# GPV1.net
KiCad netlist of a schematic drawn in EAGLE
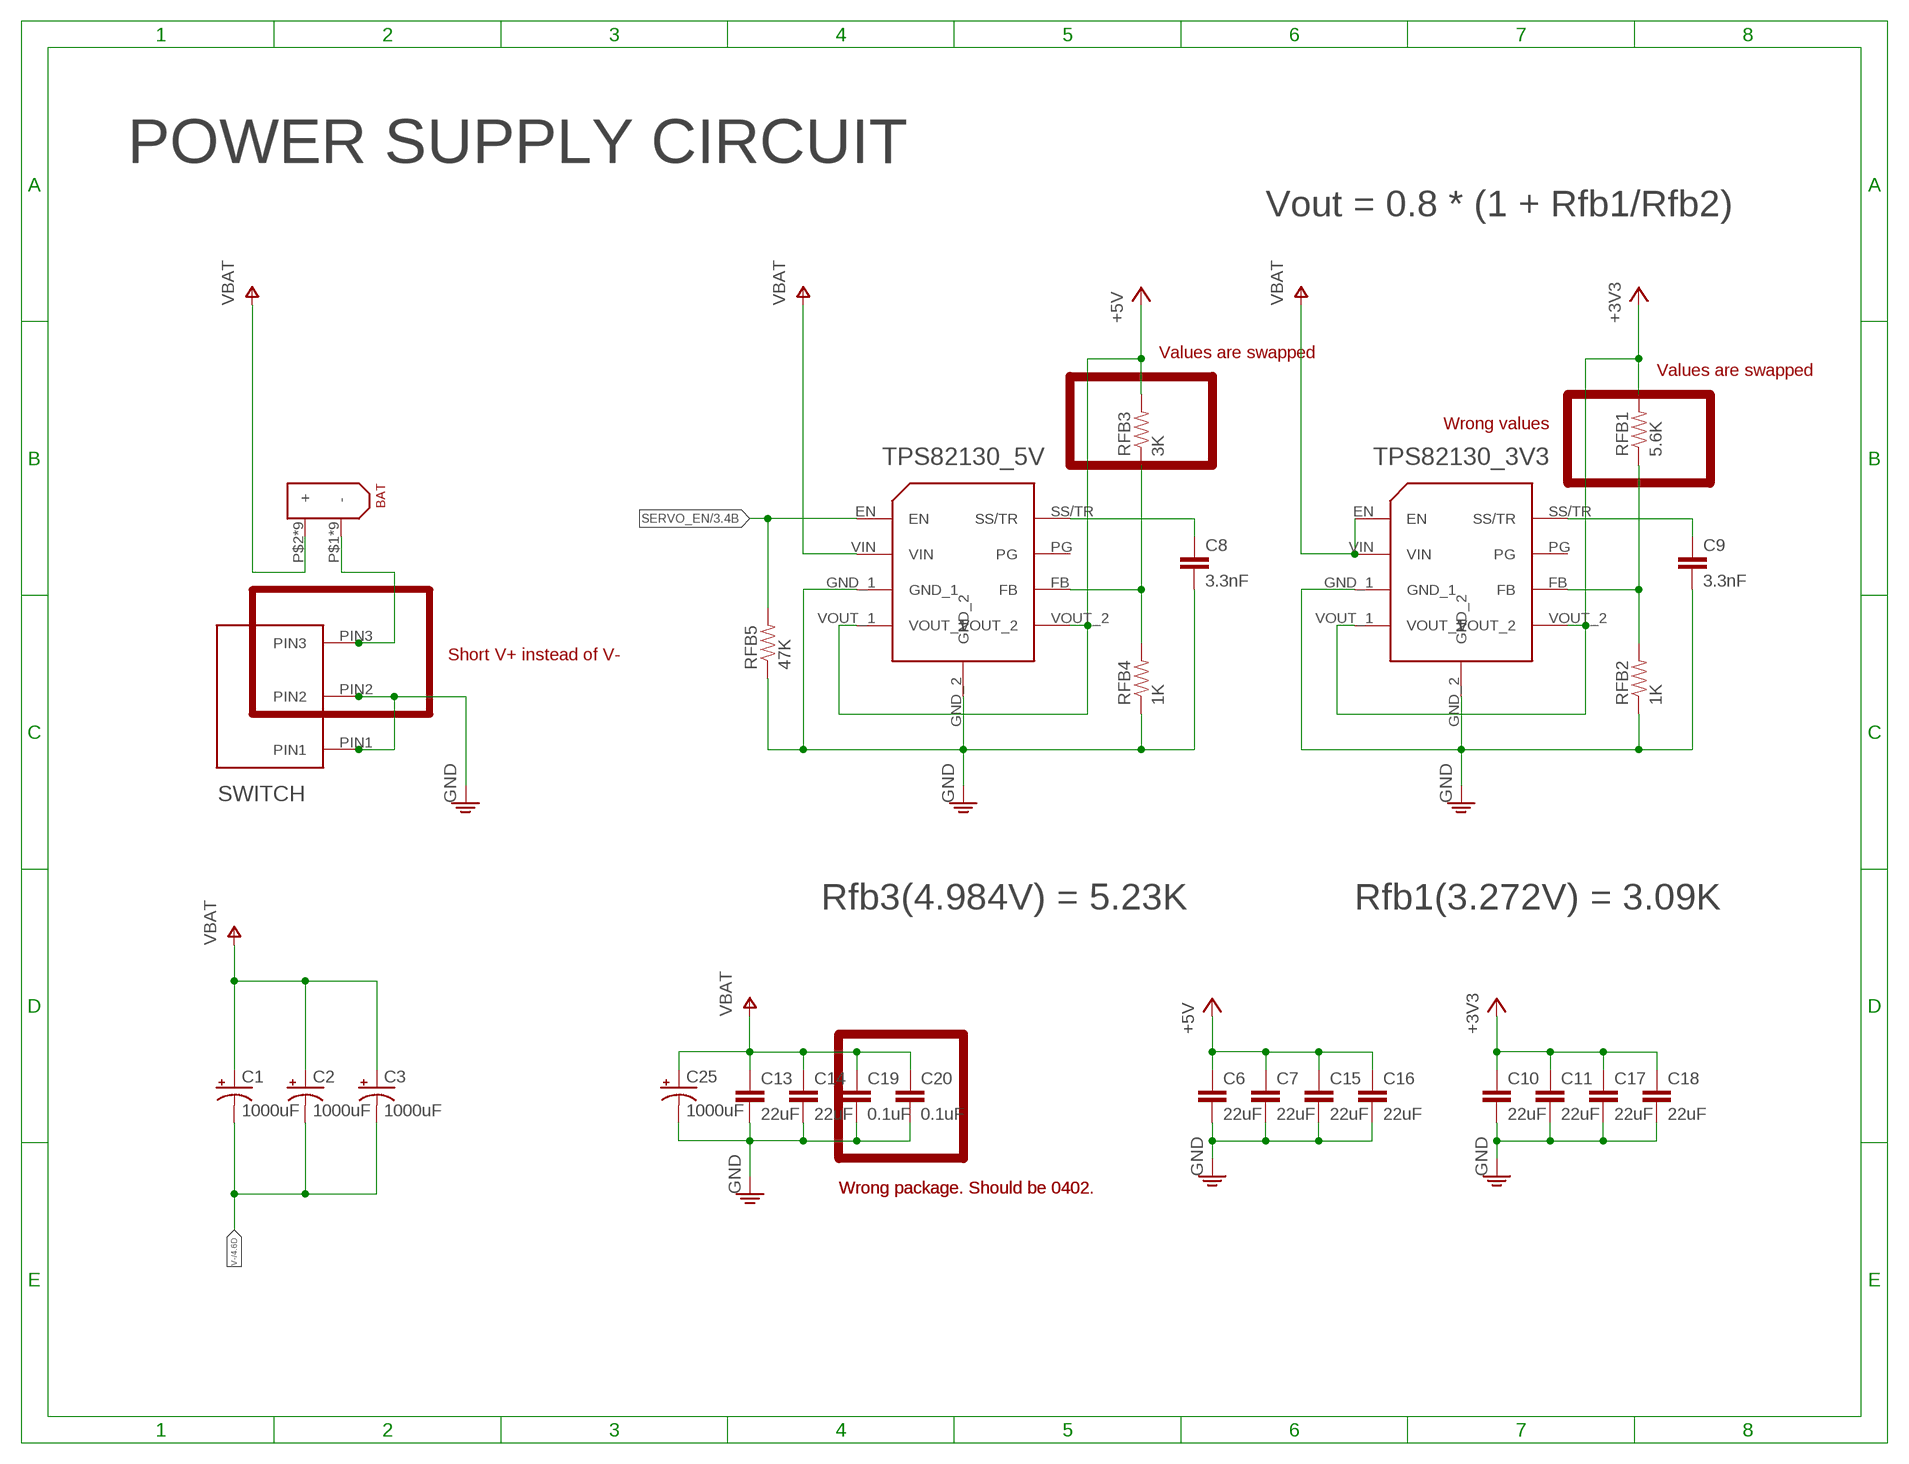
[diagram p0: schematic, sheet 1]
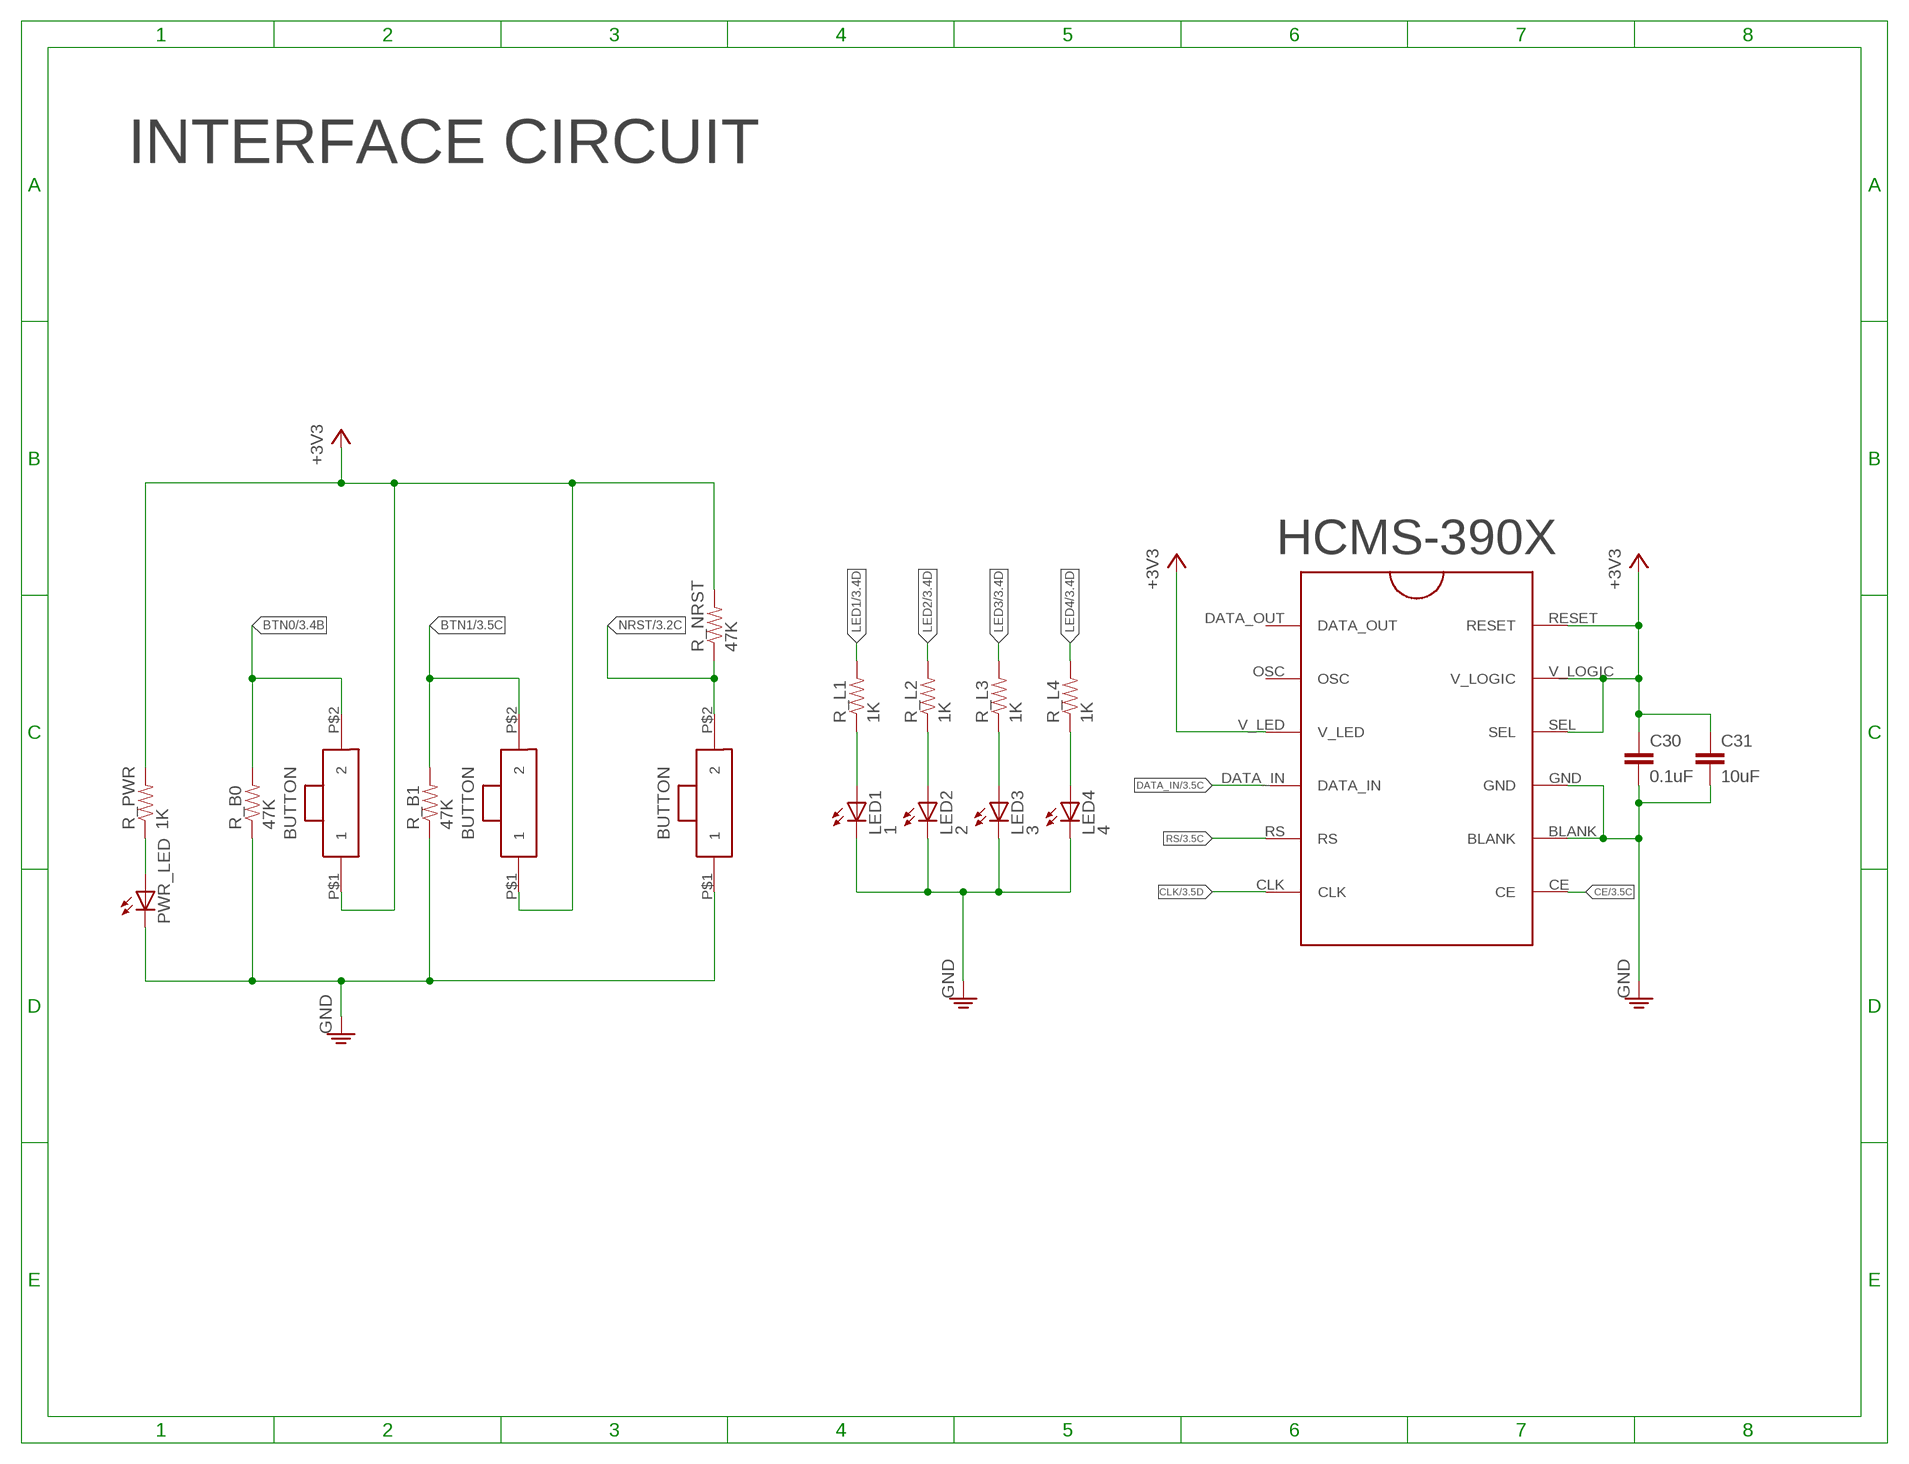
[diagram p1: schematic, sheet 2]
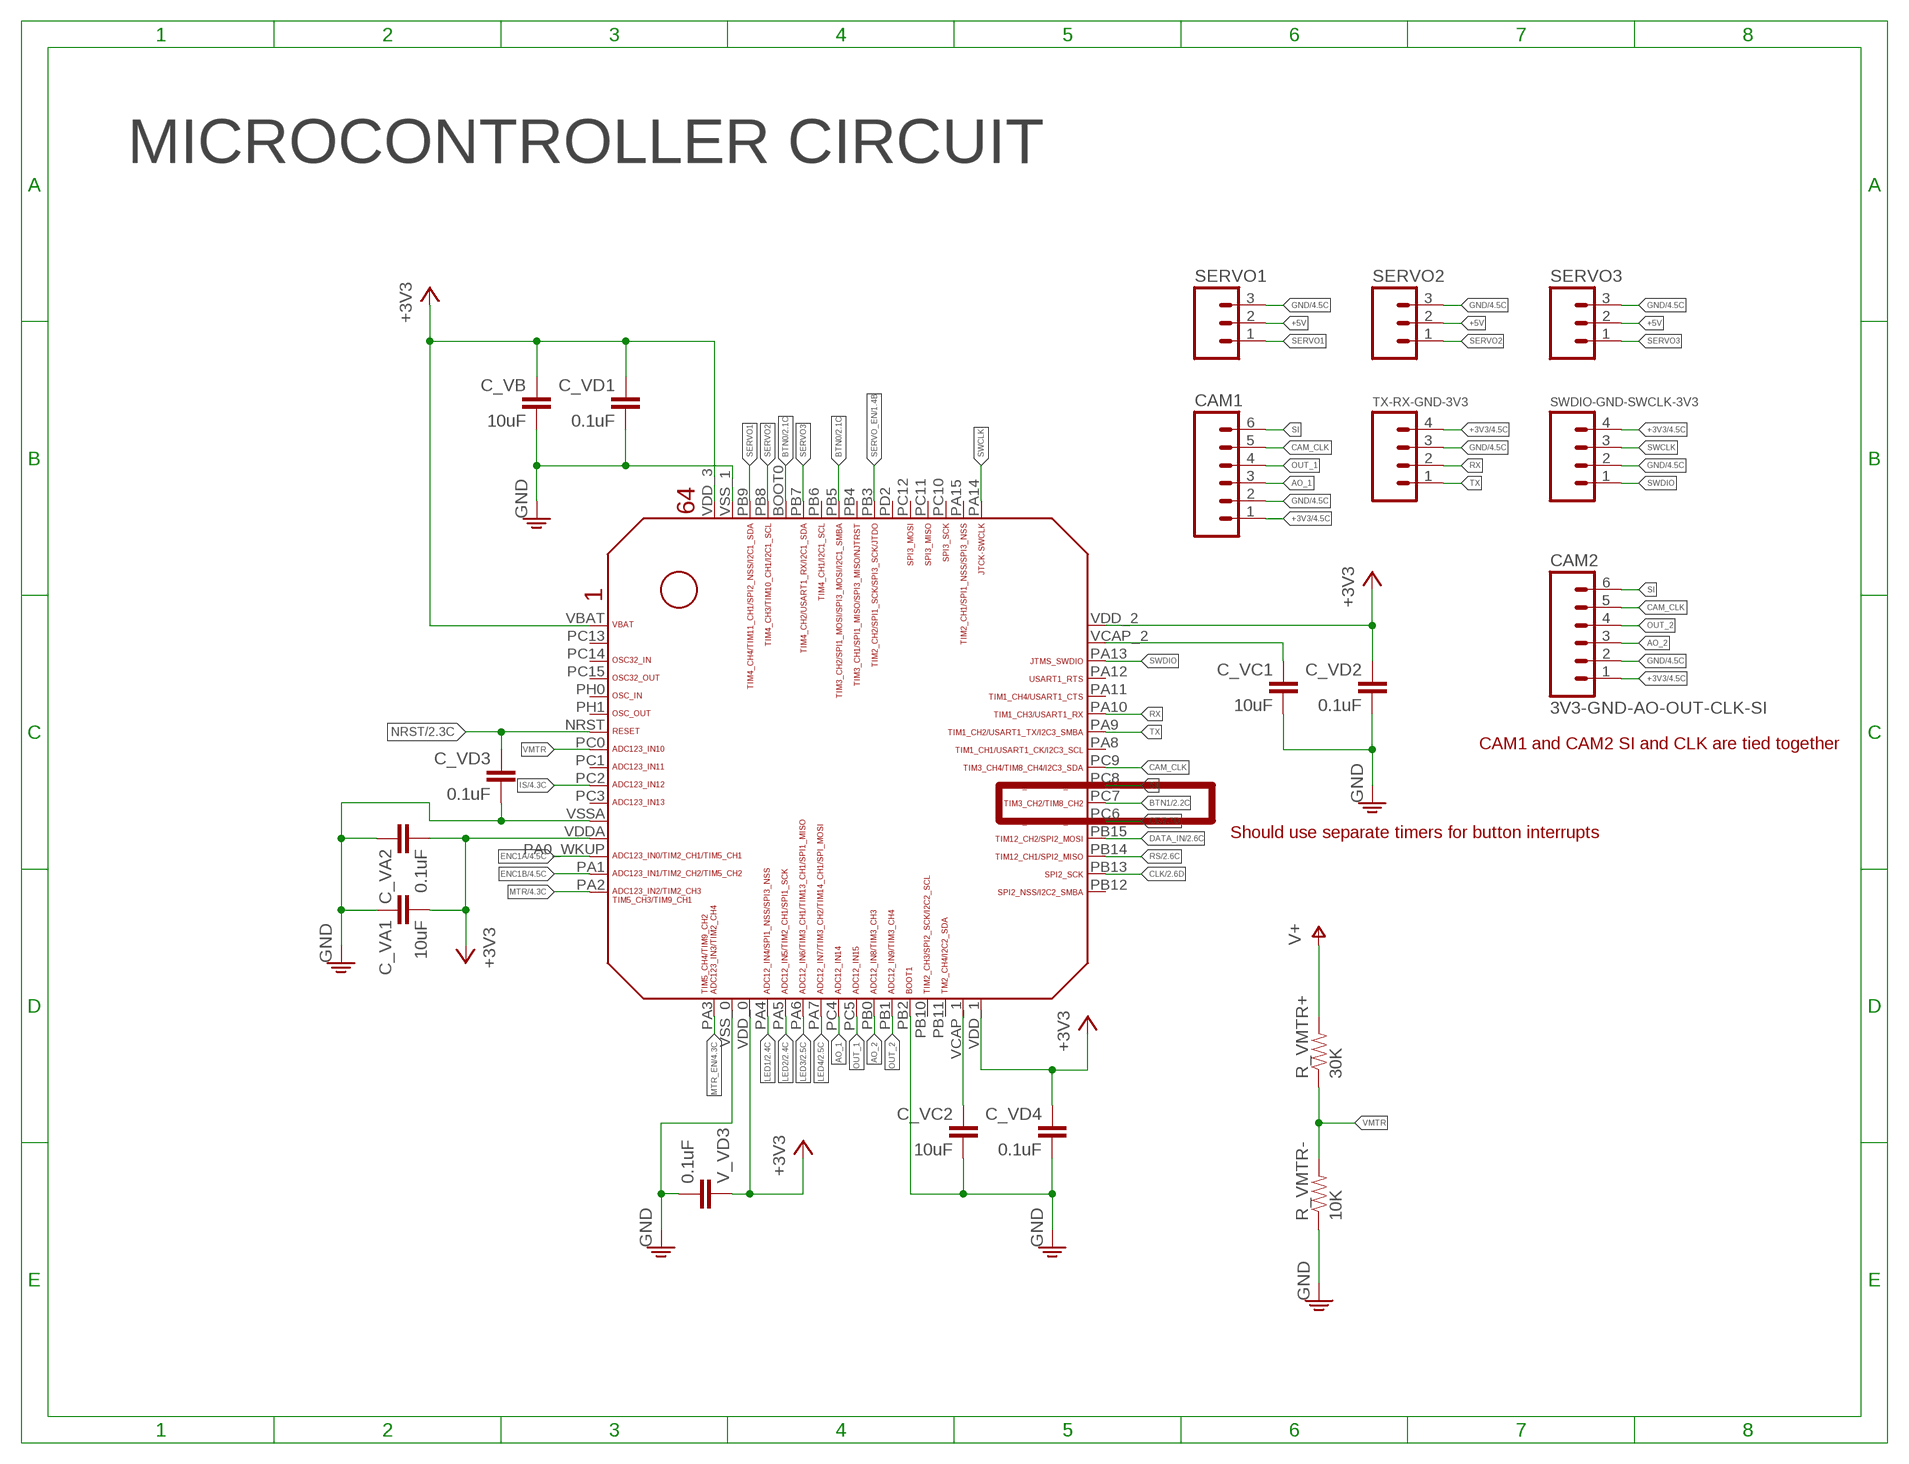
[diagram p2: schematic, sheet 3]
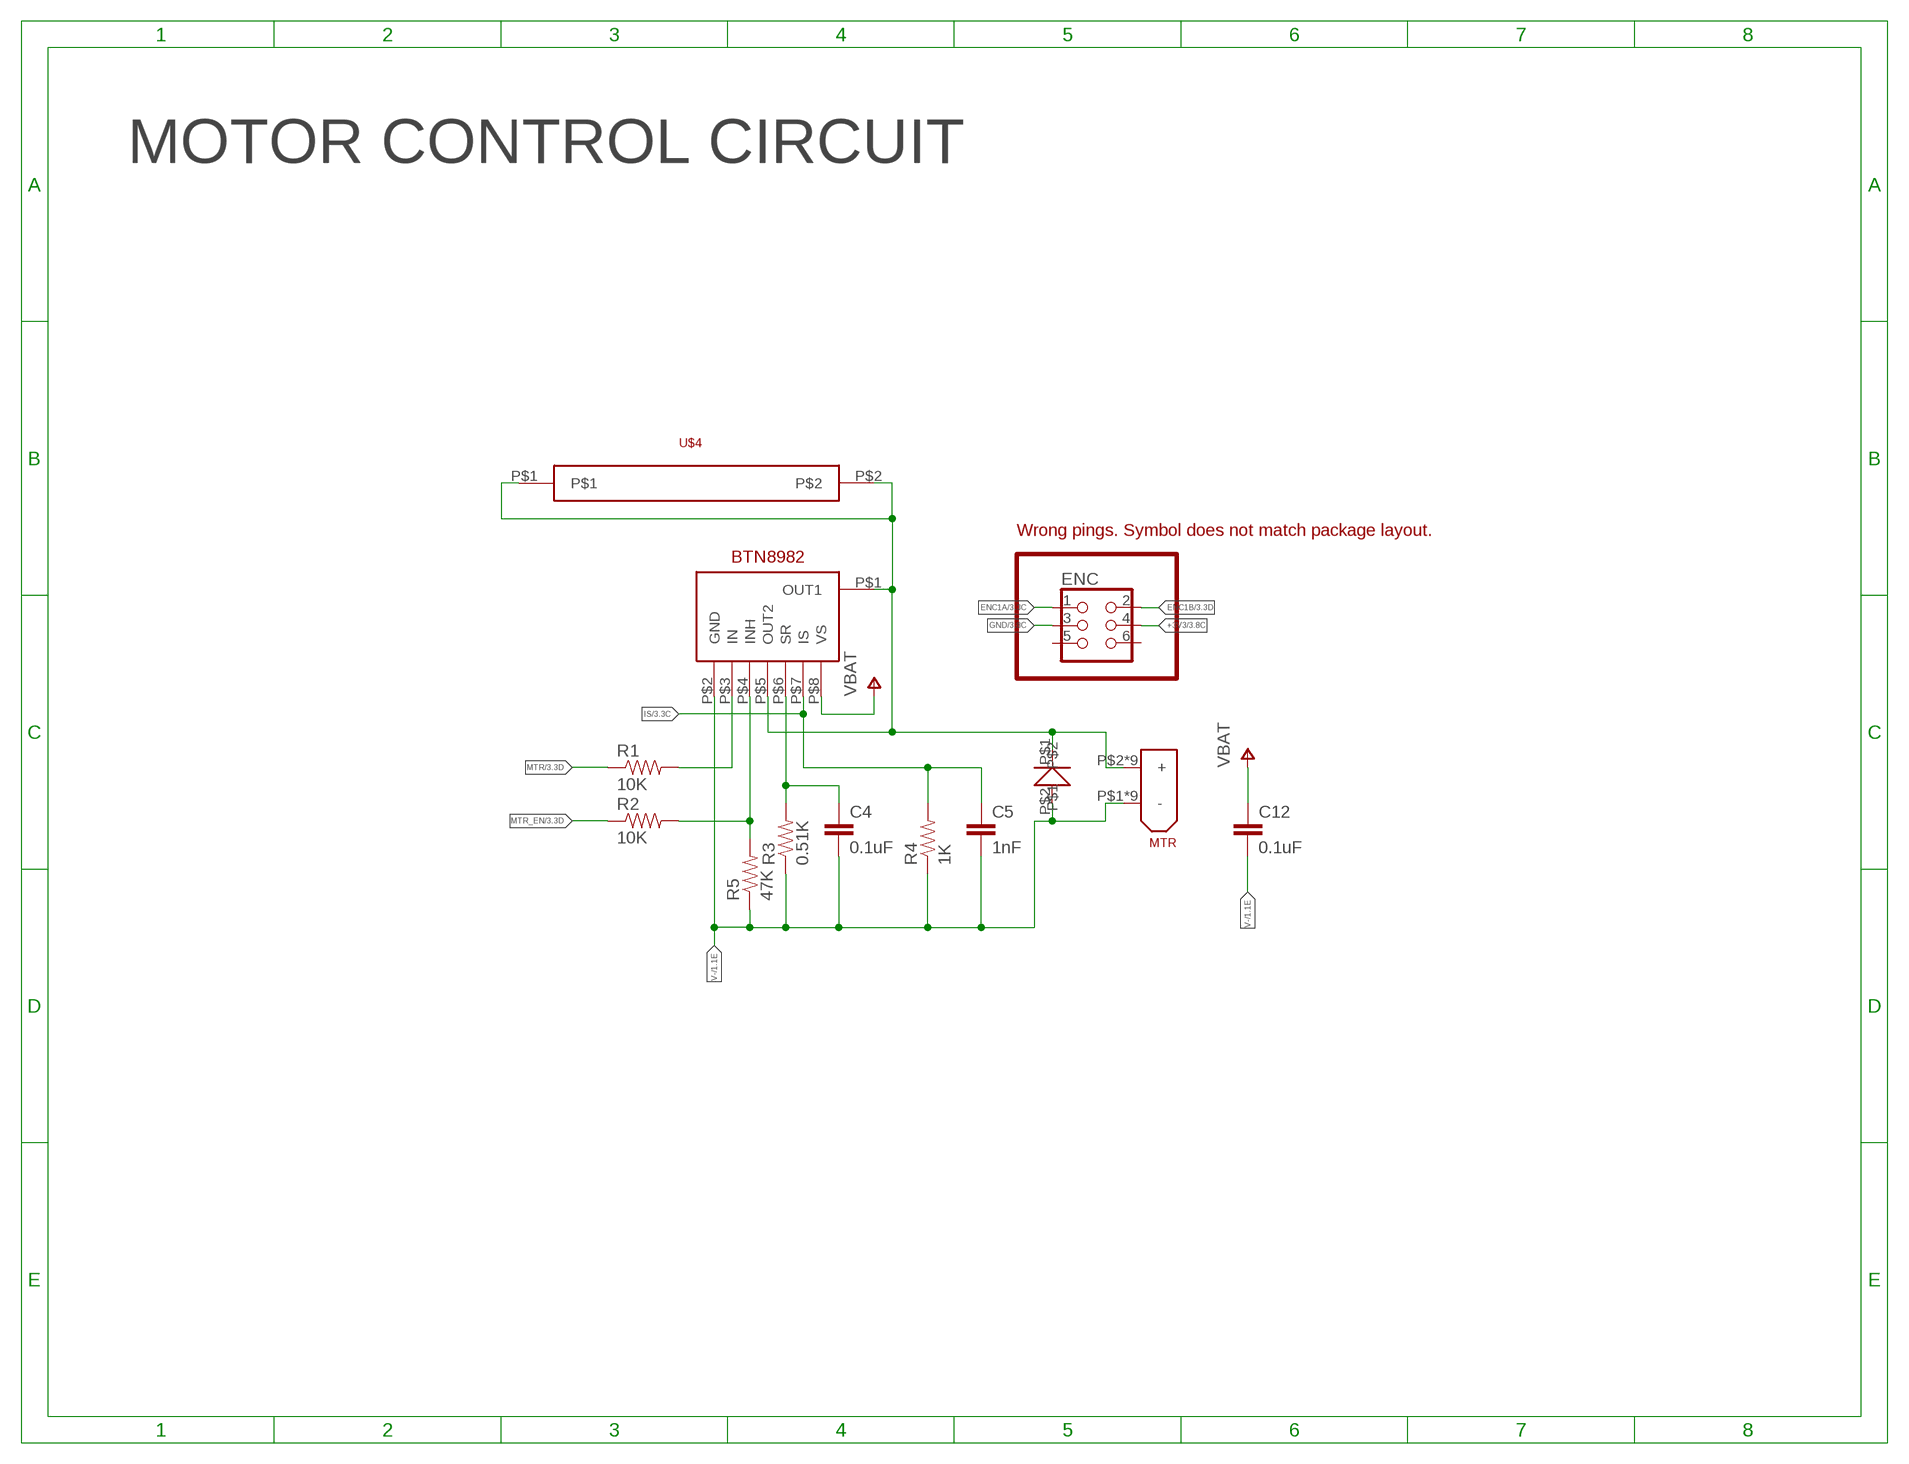
[diagram p3: schematic, sheet 4]

(export (version "E")
  (design (tool "Eeschema 10.0.6"))
  (components
    (comp (ref "BTN0")
      (value "POLOLU_BUTTON")
      (footprint "eagle-import:POLOLU_BUTTON")
      (libsource (lib "eagle-import") (part "POLOLU_BUTTON"))
    )
    (comp (ref "BTN1")
      (value "POLOLU_BUTTON")
      (footprint "eagle-import:POLOLU_BUTTON")
      (libsource (lib "eagle-import") (part "POLOLU_BUTTON"))
    )
    (comp (ref "C30")
      (value "0.1uF")
      (footprint "eagle-import:0402-CAP")
      (libsource (lib "eagle-import") (part "CAP0402-CAP"))
    )
    (comp (ref "C31")
      (value "10uF")
      (footprint "eagle-import:0402-CAP")
      (libsource (lib "eagle-import") (part "CAP0402-CAP"))
    )
    (comp (ref "HCMS-390X")
      (value "HCMS-390X")
      (footprint "eagle-import:HCMS-2903")
      (libsource (lib "eagle-import") (part "HCMS-2903"))
    )
    (comp (ref "LED1")
      (value "1")
      (footprint "eagle-import:LED-0603")
      (libsource (lib "eagle-import") (part "LED0603"))
    )
    (comp (ref "LED2")
      (value "2")
      (footprint "eagle-import:LED-0603")
      (libsource (lib "eagle-import") (part "LED0603"))
    )
    (comp (ref "LED3")
      (value "3")
      (footprint "eagle-import:LED-0603")
      (libsource (lib "eagle-import") (part "LED0603"))
    )
    (comp (ref "LED4")
      (value "4")
      (footprint "eagle-import:LED-0603")
      (libsource (lib "eagle-import") (part "LED0603"))
    )
    (comp (ref "PWR_LED")
      (value "LED0603")
      (footprint "eagle-import:LED-0603")
      (libsource (lib "eagle-import") (part "LED0603"))
    )
    (comp (ref "RESET")
      (value "NRST")
      (footprint "eagle-import:POLOLU_BUTTON")
      (libsource (lib "eagle-import") (part "POLOLU_BUTTON"))
    )
    (comp (ref "R_B0")
      (value "47K")
      (footprint "eagle-import:0402-RES")
      (libsource (lib "eagle-import") (part "RESISTOR0402-RES"))
    )
    (comp (ref "R_B1")
      (value "47K")
      (footprint "eagle-import:0402-RES")
      (libsource (lib "eagle-import") (part "RESISTOR0402-RES"))
    )
    (comp (ref "R_L1")
      (value "1K")
      (footprint "eagle-import:0402-RES")
      (libsource (lib "eagle-import") (part "RESISTOR0402-RES"))
    )
    (comp (ref "R_L2")
      (value "1K")
      (footprint "eagle-import:0402-RES")
      (libsource (lib "eagle-import") (part "RESISTOR0402-RES"))
    )
    (comp (ref "R_L3")
      (value "1K")
      (footprint "eagle-import:0402-RES")
      (libsource (lib "eagle-import") (part "RESISTOR0402-RES"))
    )
    (comp (ref "R_L4")
      (value "1K")
      (footprint "eagle-import:0402-RES")
      (libsource (lib "eagle-import") (part "RESISTOR0402-RES"))
    )
    (comp (ref "R_NRST")
      (value "47K")
      (footprint "eagle-import:0402-RES")
      (libsource (lib "eagle-import") (part "RESISTOR0402-RES"))
    )
    (comp (ref "R_PWR")
      (value "1K")
      (footprint "eagle-import:0402-RES")
      (libsource (lib "eagle-import") (part "RESISTOR0402-RES"))
    )
    (comp (ref "CAM1")
      (value "M06SIP")
      (footprint "eagle-import:1X06")
      (libsource (lib "eagle-import") (part "M06SIP"))
    )
    (comp (ref "CAM2")
      (value "3V3-GND-AO-OUT-CLK-SI")
      (footprint "eagle-import:1X06")
      (libsource (lib "eagle-import") (part "M06SIP"))
    )
    (comp (ref "C_VA1")
      (value "10uF")
      (footprint "eagle-import:0402-CAP")
      (libsource (lib "eagle-import") (part "CAP0402-CAP"))
    )
    (comp (ref "C_VA2")
      (value "0.1uF")
      (footprint "eagle-import:0402-CAP")
      (libsource (lib "eagle-import") (part "CAP0402-CAP"))
    )
    (comp (ref "C_VB")
      (value "10uF")
      (footprint "eagle-import:0402-CAP")
      (libsource (lib "eagle-import") (part "CAP0402-CAP"))
    )
    (comp (ref "C_VC1")
      (value "10uF")
      (footprint "eagle-import:0402-CAP")
      (libsource (lib "eagle-import") (part "CAP0402-CAP"))
    )
    (comp (ref "C_VC2")
      (value "10uF")
      (footprint "eagle-import:0402-CAP")
      (libsource (lib "eagle-import") (part "CAP0402-CAP"))
    )
    (comp (ref "C_VD1")
      (value "0.1uF")
      (footprint "eagle-import:0402-CAP")
      (libsource (lib "eagle-import") (part "CAP0402-CAP"))
    )
    (comp (ref "C_VD2")
      (value "0.1uF")
      (footprint "eagle-import:0402-CAP")
      (libsource (lib "eagle-import") (part "CAP0402-CAP"))
    )
    (comp (ref "C_VD3")
      (value "0.1uF")
      (footprint "eagle-import:0402-CAP")
      (libsource (lib "eagle-import") (part "CAP0402-CAP"))
    )
    (comp (ref "C_VD4")
      (value "0.1uF")
      (footprint "eagle-import:0402-CAP")
      (libsource (lib "eagle-import") (part "CAP0402-CAP"))
    )
    (comp (ref "R_VMTR+")
      (value "30K")
      (footprint "eagle-import:0402-RES")
      (libsource (lib "eagle-import") (part "RESISTOR0402-RES"))
    )
    (comp (ref "R_VMTR-")
      (value "10K")
      (footprint "eagle-import:0402-RES")
      (libsource (lib "eagle-import") (part "RESISTOR0402-RES"))
    )
    (comp (ref "SERVO1")
      (value "M03PTH")
      (footprint "eagle-import:1X03")
      (libsource (lib "eagle-import") (part "M03PTH"))
    )
    (comp (ref "SERVO2")
      (value "M03PTH")
      (footprint "eagle-import:1X03")
      (libsource (lib "eagle-import") (part "M03PTH"))
    )
    (comp (ref "SERVO3")
      (value "M03PTH")
      (footprint "eagle-import:1X03")
      (libsource (lib "eagle-import") (part "M03PTH"))
    )
    (comp (ref "STM32F4X5RG")
      (value "STM32F405/415_LQFP64")
      (footprint "eagle-import:STM32F405_415_LQFP64")
      (libsource (lib "eagle-import") (part "STM32F405/415_LQFP64"))
    )
    (comp (ref "SWDIO-GND-SWCLK-3V3")
      (value "M04PTH")
      (footprint "eagle-import:1X04")
      (libsource (lib "eagle-import") (part "M04PTH"))
    )
    (comp (ref "TX-RX-GND-3V3")
      (value "M04PTH")
      (footprint "eagle-import:1X04")
      (libsource (lib "eagle-import") (part "M04PTH"))
    )
    (comp (ref "V_VD3")
      (value "0.1uF")
      (footprint "eagle-import:0402-CAP")
      (libsource (lib "eagle-import") (part "CAP0402-CAP"))
    )
    (comp (ref "BTN8982")
      (value "BTN8982")
      (footprint "eagle-import:BTN8982")
      (libsource (lib "eagle-import") (part "BTN8982"))
    )
    (comp (ref "C4")
      (value "0.1uF")
      (footprint "eagle-import:0402-CAP")
      (libsource (lib "eagle-import") (part "CAP0402-CAP"))
    )
    (comp (ref "C5")
      (value "1nF")
      (footprint "eagle-import:0402-CAP")
      (libsource (lib "eagle-import") (part "CAP0402-CAP"))
    )
    (comp (ref "C12")
      (value "0.1uF")
      (footprint "eagle-import:0402-CAP")
      (libsource (lib "eagle-import") (part "CAP0402-CAP"))
    )
    (comp (ref "DIODE")
      (value "DIODE_DO-214AB")
      (footprint "eagle-import:DO-214AB")
      (libsource (lib "eagle-import") (part "DIODE_DO-214AB"))
    )
    (comp (ref "ENC")
      (value "PINHD-2X31")
      (footprint "eagle-import:DIN-41651")
      (libsource (lib "eagle-import") (part "PINHD-2X31"))
    )
    (comp (ref "MTR")
      (value "XT-60")
      (footprint "eagle-import:XT-60")
      (libsource (lib "eagle-import") (part "XT-60"))
    )
    (comp (ref "R1")
      (value "10K")
      (footprint "eagle-import:0402-RES")
      (libsource (lib "eagle-import") (part "RESISTOR0402-RES"))
    )
    (comp (ref "R2")
      (value "10K")
      (footprint "eagle-import:0402-RES")
      (libsource (lib "eagle-import") (part "RESISTOR0402-RES"))
    )
    (comp (ref "R3")
      (value "0.51K")
      (footprint "eagle-import:0402-RES")
      (libsource (lib "eagle-import") (part "RESISTOR0402-RES"))
    )
    (comp (ref "R4")
      (value "1K")
      (footprint "eagle-import:0402-RES")
      (libsource (lib "eagle-import") (part "RESISTOR0402-RES"))
    )
    (comp (ref "R5")
      (value "47K")
      (footprint "eagle-import:0402-RES")
      (libsource (lib "eagle-import") (part "RESISTOR0402-RES"))
    )
    (comp (ref "U$4")
      (value "HEATSINK_TO-263")
      (footprint "eagle-import:HEATSINK_TO-263")
      (libsource (lib "eagle-import") (part "HEATSINK_TO-263"))
    )
    (comp (ref "BAT")
      (value "XT-60")
      (footprint "eagle-import:XT-60")
      (libsource (lib "eagle-import") (part "XT-60"))
    )
    (comp (ref "C1")
      (value "1000uF")
      (footprint "eagle-import:PANASONIC_H13")
      (libsource (lib "eagle-import") (part "CAP_POLH13"))
    )
    (comp (ref "C2")
      (value "1000uF")
      (footprint "eagle-import:PANASONIC_H13")
      (libsource (lib "eagle-import") (part "CAP_POLH13"))
    )
    (comp (ref "C3")
      (value "1000uF")
      (footprint "eagle-import:PANASONIC_H13")
      (libsource (lib "eagle-import") (part "CAP_POLH13"))
    )
    (comp (ref "C6")
      (value "22uF")
      (footprint "eagle-import:0805")
      (libsource (lib "eagle-import") (part "CAP0805"))
    )
    (comp (ref "C7")
      (value "22uF")
      (footprint "eagle-import:0805")
      (libsource (lib "eagle-import") (part "CAP0805"))
    )
    (comp (ref "C8")
      (value "3.3nF")
      (footprint "eagle-import:0402-CAP")
      (libsource (lib "eagle-import") (part "CAP0402-CAP"))
    )
    (comp (ref "C9")
      (value "3.3nF")
      (footprint "eagle-import:0402-CAP")
      (libsource (lib "eagle-import") (part "CAP0402-CAP"))
    )
    (comp (ref "C10")
      (value "22uF")
      (footprint "eagle-import:0805")
      (libsource (lib "eagle-import") (part "CAP0805"))
    )
    (comp (ref "C11")
      (value "22uF")
      (footprint "eagle-import:0805")
      (libsource (lib "eagle-import") (part "CAP0805"))
    )
    (comp (ref "C13")
      (value "22uF")
      (footprint "eagle-import:0805")
      (libsource (lib "eagle-import") (part "CAP0805"))
    )
    (comp (ref "C14")
      (value "22uF")
      (footprint "eagle-import:0805")
      (libsource (lib "eagle-import") (part "CAP0805"))
    )
    (comp (ref "C15")
      (value "22uF")
      (footprint "eagle-import:0805")
      (libsource (lib "eagle-import") (part "CAP0805"))
    )
    (comp (ref "C16")
      (value "22uF")
      (footprint "eagle-import:0805")
      (libsource (lib "eagle-import") (part "CAP0805"))
    )
    (comp (ref "C17")
      (value "22uF")
      (footprint "eagle-import:0805")
      (libsource (lib "eagle-import") (part "CAP0805"))
    )
    (comp (ref "C18")
      (value "22uF")
      (footprint "eagle-import:0805")
      (libsource (lib "eagle-import") (part "CAP0805"))
    )
    (comp (ref "C19")
      (value "0.1uF")
      (footprint "eagle-import:0805")
      (libsource (lib "eagle-import") (part "CAP0805"))
    )
    (comp (ref "C20")
      (value "0.1uF")
      (footprint "eagle-import:0805")
      (libsource (lib "eagle-import") (part "CAP0805"))
    )
    (comp (ref "C25")
      (value "1000uF")
      (footprint "eagle-import:PANASONIC_H13")
      (libsource (lib "eagle-import") (part "CAP_POLH13"))
    )
    (comp (ref "ON<-->OFF")
      (value "TS02_SWITCH")
      (footprint "eagle-import:TS02_SWITCH")
      (libsource (lib "eagle-import") (part "TS02_SWITCH"))
    )
    (comp (ref "RFB1")
      (value "5.6K")
      (footprint "eagle-import:0402-RES")
      (libsource (lib "eagle-import") (part "RESISTOR0402-RES"))
    )
    (comp (ref "RFB2")
      (value "1K")
      (footprint "eagle-import:0402-RES")
      (libsource (lib "eagle-import") (part "RESISTOR0402-RES"))
    )
    (comp (ref "RFB3")
      (value "3K")
      (footprint "eagle-import:0402-RES")
      (libsource (lib "eagle-import") (part "RESISTOR0402-RES"))
    )
    (comp (ref "RFB4")
      (value "1K")
      (footprint "eagle-import:0402-RES")
      (libsource (lib "eagle-import") (part "RESISTOR0402-RES"))
    )
    (comp (ref "RFB5")
      (value "47K")
      (footprint "eagle-import:0402-RES")
      (libsource (lib "eagle-import") (part "RESISTOR0402-RES"))
    )
    (comp (ref "TPS82130_3V3")
      (value "TPS82130")
      (footprint "eagle-import:TPS82130")
      (libsource (lib "eagle-import") (part "TPS82130"))
    )
    (comp (ref "TPS82130_5V")
      (value "TPS82130")
      (footprint "eagle-import:TPS82130")
      (libsource (lib "eagle-import") (part "TPS82130"))
    )
  )
  (nets
    (net (code "1") (name "+3V3") (class "Default")
      (node (ref "BTN0") (pin "P$1") (pinfunction "1_P$1") (pintype "bidirectional"))
      (node (ref "BTN1") (pin "P$1") (pinfunction "1_P$1") (pintype "bidirectional"))
      (node (ref "C10") (pin "1") (pinfunction "1_1") (pintype "passive"))
      (node (ref "C11") (pin "1") (pinfunction "1_1") (pintype "passive"))
      (node (ref "C17") (pin "1") (pinfunction "1_1") (pintype "passive"))
      (node (ref "C18") (pin "1") (pinfunction "1_1") (pintype "passive"))
      (node (ref "C30") (pin "1") (pinfunction "1_1") (pintype "passive"))
      (node (ref "C31") (pin "1") (pinfunction "1_1") (pintype "passive"))
      (node (ref "CAM1") (pin "1") (pinfunction "1_1") (pintype "passive"))
      (node (ref "CAM2") (pin "1") (pinfunction "1_1") (pintype "passive"))
      (node (ref "C_VA1") (pin "2") (pinfunction "2_2") (pintype "passive"))
      (node (ref "C_VA2") (pin "2") (pinfunction "2_2") (pintype "passive"))
      (node (ref "C_VB") (pin "1") (pinfunction "1_1") (pintype "passive"))
      (node (ref "C_VD1") (pin "1") (pinfunction "1_1") (pintype "passive"))
      (node (ref "C_VD2") (pin "1") (pinfunction "1_1") (pintype "passive"))
      (node (ref "C_VD4") (pin "1") (pinfunction "1_1") (pintype "passive"))
      (node (ref "ENC") (pin "4") (pinfunction "4_4") (pintype "passive"))
      (node (ref "HCMS-390X") (pin "RESET") (pinfunction "RESET_RESET") (pintype "bidirectional"))
      (node (ref "HCMS-390X") (pin "SEL") (pinfunction "SEL_SEL") (pintype "bidirectional"))
      (node (ref "HCMS-390X") (pin "V_LED") (pinfunction "V_LED_V_LED") (pintype "bidirectional"))
      (node (ref "HCMS-390X") (pin "V_LOGIC") (pinfunction "V_LOGIC_V_LOGIC") (pintype "bidirectional"))
      (node (ref "RFB1") (pin "2") (pinfunction "2_2") (pintype "passive"))
      (node (ref "R_NRST") (pin "2") (pinfunction "2_2") (pintype "passive"))
      (node (ref "R_PWR") (pin "2") (pinfunction "2_2") (pintype "passive"))
      (node (ref "STM32F4X5RG") (pin "VBAT") (pinfunction "VBAT_VBAT") (pintype "bidirectional"))
      (node (ref "STM32F4X5RG") (pin "VDDA") (pinfunction "VDDA_VDDA") (pintype "bidirectional"))
      (node (ref "STM32F4X5RG") (pin "VDD_0") (pinfunction "VDD_0_VDD_0") (pintype "bidirectional"))
      (node (ref "STM32F4X5RG") (pin "VDD_1") (pinfunction "VDD_1_VDD_1") (pintype "bidirectional"))
      (node (ref "STM32F4X5RG") (pin "VDD_2") (pinfunction "VDD_2_VDD_2") (pintype "bidirectional"))
      (node (ref "STM32F4X5RG") (pin "VDD_3") (pinfunction "VDD_3_VDD_3") (pintype "bidirectional"))
      (node (ref "SWDIO-GND-SWCLK-3V3") (pin "4") (pinfunction "4_4") (pintype "passive"))
      (node (ref "TPS82130_3V3") (pin "VOUT_1") (pinfunction "VOUT_1_VOUT_1") (pintype "bidirectional"))
      (node (ref "TPS82130_3V3") (pin "VOUT_2") (pinfunction "VOUT_2_VOUT_2") (pintype "bidirectional"))
      (node (ref "TX-RX-GND-3V3") (pin "4") (pinfunction "4_4") (pintype "passive"))
      (node (ref "V_VD3") (pin "1") (pinfunction "1_1") (pintype "passive"))
    )
    (net (code "2") (name "+5V") (class "Default")
      (node (ref "C15") (pin "1") (pinfunction "1_1") (pintype "passive"))
      (node (ref "C16") (pin "1") (pinfunction "1_1") (pintype "passive"))
      (node (ref "C6") (pin "1") (pinfunction "1_1") (pintype "passive"))
      (node (ref "C7") (pin "1") (pinfunction "1_1") (pintype "passive"))
      (node (ref "RFB3") (pin "2") (pinfunction "2_2") (pintype "passive"))
      (node (ref "SERVO1") (pin "2") (pinfunction "2_2") (pintype "passive"))
      (node (ref "SERVO2") (pin "2") (pinfunction "2_2") (pintype "passive"))
      (node (ref "SERVO3") (pin "2") (pinfunction "2_2") (pintype "passive"))
      (node (ref "TPS82130_5V") (pin "VOUT_1") (pinfunction "VOUT_1_VOUT_1") (pintype "bidirectional"))
      (node (ref "TPS82130_5V") (pin "VOUT_2") (pinfunction "VOUT_2_VOUT_2") (pintype "bidirectional"))
    )
    (net (code "3") (name "AO_1") (class "Default")
      (node (ref "CAM1") (pin "3") (pinfunction "3_3") (pintype "passive"))
      (node (ref "STM32F4X5RG") (pin "PC4") (pinfunction "PC4_PC4") (pintype "bidirectional"))
    )
    (net (code "4") (name "AO_2") (class "Default")
      (node (ref "CAM2") (pin "3") (pinfunction "3_3") (pintype "passive"))
      (node (ref "STM32F4X5RG") (pin "PB0") (pinfunction "PB0_PB0") (pintype "bidirectional"))
    )
    (net (code "5") (name "BTN0") (class "Default")
      (node (ref "BTN0") (pin "P$2") (pinfunction "2_P$2") (pintype "bidirectional"))
      (node (ref "R_B0") (pin "2") (pinfunction "2_2") (pintype "passive"))
      (node (ref "STM32F4X5RG") (pin "BOOT0") (pinfunction "BOOT0_BOOT0") (pintype "bidirectional"))
      (node (ref "STM32F4X5RG") (pin "PB5") (pinfunction "PB5_PB5") (pintype "bidirectional"))
    )
    (net (code "6") (name "BTN1") (class "Default")
      (node (ref "BTN1") (pin "P$2") (pinfunction "2_P$2") (pintype "bidirectional"))
      (node (ref "R_B1") (pin "2") (pinfunction "2_2") (pintype "passive"))
      (node (ref "STM32F4X5RG") (pin "PC7") (pinfunction "PC7_PC7") (pintype "bidirectional"))
    )
    (net (code "7") (name "CAM_CLK") (class "Default")
      (node (ref "CAM1") (pin "5") (pinfunction "5_5") (pintype "passive"))
      (node (ref "CAM2") (pin "5") (pinfunction "5_5") (pintype "passive"))
      (node (ref "STM32F4X5RG") (pin "PC9") (pinfunction "PC9_PC9") (pintype "bidirectional"))
    )
    (net (code "8") (name "CE") (class "Default")
      (node (ref "HCMS-390X") (pin "CE") (pinfunction "CE_CE") (pintype "bidirectional"))
      (node (ref "STM32F4X5RG") (pin "PC6") (pinfunction "PC6_PC6") (pintype "bidirectional"))
    )
    (net (code "9") (name "CLK") (class "Default")
      (node (ref "HCMS-390X") (pin "CLK") (pinfunction "CLK_CLK") (pintype "bidirectional"))
      (node (ref "STM32F4X5RG") (pin "PB13") (pinfunction "PB13_PB13") (pintype "bidirectional"))
    )
    (net (code "10") (name "DATA_IN") (class "Default")
      (node (ref "HCMS-390X") (pin "DATA_IN") (pinfunction "DATA_IN_DATA_IN") (pintype "bidirectional"))
      (node (ref "STM32F4X5RG") (pin "PB15") (pinfunction "PB15_PB15") (pintype "bidirectional"))
    )
    (net (code "11") (name "ENC1A") (class "Default")
      (node (ref "ENC") (pin "1") (pinfunction "1_1") (pintype "passive"))
      (node (ref "STM32F4X5RG") (pin "PA0_WKUP") (pinfunction "PA0_AKUP_PA0_WKUP") (pintype "bidirectional"))
    )
    (net (code "12") (name "ENC1B") (class "Default")
      (node (ref "ENC") (pin "2") (pinfunction "2_2") (pintype "passive"))
      (node (ref "STM32F4X5RG") (pin "PA1") (pinfunction "PA1_PA1") (pintype "bidirectional"))
    )
    (net (code "13") (name "GND") (class "Default")
      (node (ref "C10") (pin "2") (pinfunction "2_2") (pintype "passive"))
      (node (ref "C11") (pin "2") (pinfunction "2_2") (pintype "passive"))
      (node (ref "C13") (pin "2") (pinfunction "2_2") (pintype "passive"))
      (node (ref "C14") (pin "2") (pinfunction "2_2") (pintype "passive"))
      (node (ref "C15") (pin "2") (pinfunction "2_2") (pintype "passive"))
      (node (ref "C16") (pin "2") (pinfunction "2_2") (pintype "passive"))
      (node (ref "C17") (pin "2") (pinfunction "2_2") (pintype "passive"))
      (node (ref "C18") (pin "2") (pinfunction "2_2") (pintype "passive"))
      (node (ref "C19") (pin "2") (pinfunction "2_2") (pintype "passive"))
      (node (ref "C20") (pin "2") (pinfunction "2_2") (pintype "passive"))
      (node (ref "C25") (pin "-") (pinfunction "-_-") (pintype "passive"))
      (node (ref "C30") (pin "2") (pinfunction "2_2") (pintype "passive"))
      (node (ref "C31") (pin "2") (pinfunction "2_2") (pintype "passive"))
      (node (ref "C6") (pin "2") (pinfunction "2_2") (pintype "passive"))
      (node (ref "C7") (pin "2") (pinfunction "2_2") (pintype "passive"))
      (node (ref "C8") (pin "2") (pinfunction "2_2") (pintype "passive"))
      (node (ref "C9") (pin "2") (pinfunction "2_2") (pintype "passive"))
      (node (ref "CAM1") (pin "2") (pinfunction "2_2") (pintype "passive"))
      (node (ref "CAM2") (pin "2") (pinfunction "2_2") (pintype "passive"))
      (node (ref "C_VA1") (pin "1") (pinfunction "1_1") (pintype "passive"))
      (node (ref "C_VA2") (pin "1") (pinfunction "1_1") (pintype "passive"))
      (node (ref "C_VB") (pin "2") (pinfunction "2_2") (pintype "passive"))
      (node (ref "C_VC1") (pin "2") (pinfunction "2_2") (pintype "passive"))
      (node (ref "C_VC2") (pin "2") (pinfunction "2_2") (pintype "passive"))
      (node (ref "C_VD1") (pin "2") (pinfunction "2_2") (pintype "passive"))
      (node (ref "C_VD2") (pin "2") (pinfunction "2_2") (pintype "passive"))
      (node (ref "C_VD3") (pin "2") (pinfunction "2_2") (pintype "passive"))
      (node (ref "C_VD4") (pin "2") (pinfunction "2_2") (pintype "passive"))
      (node (ref "ENC") (pin "3") (pinfunction "3_3") (pintype "passive"))
      (node (ref "HCMS-390X") (pin "BLANK") (pinfunction "BLANK_BLANK") (pintype "bidirectional"))
      (node (ref "HCMS-390X") (pin "GND") (pinfunction "GND_GND") (pintype "bidirectional"))
      (node (ref "LED1") (pin "C") (pinfunction "C_C") (pintype "passive"))
      (node (ref "LED2") (pin "C") (pinfunction "C_C") (pintype "passive"))
      (node (ref "LED3") (pin "C") (pinfunction "C_C") (pintype "passive"))
      (node (ref "LED4") (pin "C") (pinfunction "C_C") (pintype "passive"))
      (node (ref "ON<-->OFF") (pin "PIN1") (pinfunction "PIN1_PIN1") (pintype "bidirectional"))
      (node (ref "ON<-->OFF") (pin "PIN2") (pinfunction "PIN2_PIN2") (pintype "bidirectional"))
      (node (ref "PWR_LED") (pin "C") (pinfunction "C_C") (pintype "passive"))
      (node (ref "RESET") (pin "P$1") (pinfunction "1_P$1") (pintype "bidirectional"))
      (node (ref "RFB2") (pin "1") (pinfunction "1_1") (pintype "passive"))
      (node (ref "RFB4") (pin "1") (pinfunction "1_1") (pintype "passive"))
      (node (ref "RFB5") (pin "1") (pinfunction "1_1") (pintype "passive"))
      (node (ref "R_B0") (pin "1") (pinfunction "1_1") (pintype "passive"))
      (node (ref "R_B1") (pin "1") (pinfunction "1_1") (pintype "passive"))
      (node (ref "R_VMTR-") (pin "1") (pinfunction "1_1") (pintype "passive"))
      (node (ref "SERVO1") (pin "3") (pinfunction "3_3") (pintype "passive"))
      (node (ref "SERVO2") (pin "3") (pinfunction "3_3") (pintype "passive"))
      (node (ref "SERVO3") (pin "3") (pinfunction "3_3") (pintype "passive"))
      (node (ref "STM32F4X5RG") (pin "PB2") (pinfunction "PB2_PB2") (pintype "bidirectional"))
      (node (ref "STM32F4X5RG") (pin "VSSA") (pinfunction "VSSA_VSSA") (pintype "bidirectional"))
      (node (ref "STM32F4X5RG") (pin "VSS_0") (pinfunction "VSS_0_VSS_0") (pintype "bidirectional"))
      (node (ref "STM32F4X5RG") (pin "VSS_1") (pinfunction "VSS_1_VSS_1") (pintype "bidirectional"))
      (node (ref "SWDIO-GND-SWCLK-3V3") (pin "2") (pinfunction "2_2") (pintype "passive"))
      (node (ref "TPS82130_3V3") (pin "GND_1") (pinfunction "GND_1_GND_1") (pintype "bidirectional"))
      (node (ref "TPS82130_3V3") (pin "GND_2") (pinfunction "GND_2_GND_2") (pintype "bidirectional"))
      (node (ref "TPS82130_5V") (pin "GND_1") (pinfunction "GND_1_GND_1") (pintype "bidirectional"))
      (node (ref "TPS82130_5V") (pin "GND_2") (pinfunction "GND_2_GND_2") (pintype "bidirectional"))
      (node (ref "TX-RX-GND-3V3") (pin "3") (pinfunction "3_3") (pintype "passive"))
      (node (ref "V_VD3") (pin "2") (pinfunction "2_2") (pintype "passive"))
    )
    (net (code "14") (name "IS") (class "Default")
      (node (ref "BTN8982") (pin "P$7") (pinfunction "IS_P$7") (pintype "bidirectional"))
      (node (ref "C5") (pin "1") (pinfunction "1_1") (pintype "passive"))
      (node (ref "R4") (pin "2") (pinfunction "2_2") (pintype "passive"))
      (node (ref "STM32F4X5RG") (pin "PC2") (pinfunction "PC2_PC2") (pintype "bidirectional"))
    )
    (net (code "15") (name "LED1") (class "Default")
      (node (ref "R_L1") (pin "2") (pinfunction "2_2") (pintype "passive"))
      (node (ref "STM32F4X5RG") (pin "PA4") (pinfunction "PA4_PA4") (pintype "bidirectional"))
    )
    (net (code "16") (name "LED2") (class "Default")
      (node (ref "R_L2") (pin "2") (pinfunction "2_2") (pintype "passive"))
      (node (ref "STM32F4X5RG") (pin "PA5") (pinfunction "PA5_PA5") (pintype "bidirectional"))
    )
    (net (code "17") (name "LED3") (class "Default")
      (node (ref "R_L3") (pin "2") (pinfunction "2_2") (pintype "passive"))
      (node (ref "STM32F4X5RG") (pin "PA6") (pinfunction "PA6_PA6") (pintype "bidirectional"))
    )
    (net (code "18") (name "LED4") (class "Default")
      (node (ref "R_L4") (pin "2") (pinfunction "2_2") (pintype "passive"))
      (node (ref "STM32F4X5RG") (pin "PA7") (pinfunction "PA7_PA7") (pintype "bidirectional"))
    )
    (net (code "19") (name "MTR") (class "Default")
      (node (ref "R1") (pin "1") (pinfunction "1_1") (pintype "passive"))
      (node (ref "STM32F4X5RG") (pin "PA2") (pinfunction "PA2_PA2") (pintype "bidirectional"))
    )
    (net (code "20") (name "MTR_EN") (class "Default")
      (node (ref "R2") (pin "1") (pinfunction "1_1") (pintype "passive"))
      (node (ref "STM32F4X5RG") (pin "PA3") (pinfunction "PA3_PA3") (pintype "bidirectional"))
    )
    (net (code "21") (name "NRST") (class "Default")
      (node (ref "C_VD3") (pin "1") (pinfunction "1_1") (pintype "passive"))
      (node (ref "RESET") (pin "P$2") (pinfunction "2_P$2") (pintype "bidirectional"))
      (node (ref "R_NRST") (pin "1") (pinfunction "1_1") (pintype "passive"))
      (node (ref "STM32F4X5RG") (pin "NRST") (pinfunction "NRST_NRST") (pintype "bidirectional"))
    )
    (net (code "22") (name "Net-(BTN8982-IN)") (class "Default")
      (node (ref "BTN8982") (pin "P$3") (pinfunction "IN_P$3") (pintype "bidirectional"))
      (node (ref "R1") (pin "2") (pinfunction "2_2") (pintype "passive"))
    )
    (net (code "23") (name "Net-(BTN8982-INH)") (class "Default")
      (node (ref "BTN8982") (pin "P$4") (pinfunction "INH_P$4") (pintype "bidirectional"))
      (node (ref "R2") (pin "2") (pinfunction "2_2") (pintype "passive"))
      (node (ref "R5") (pin "2") (pinfunction "2_2") (pintype "passive"))
    )
    (net (code "24") (name "Net-(BTN8982-OUT1)") (class "Default")
      (node (ref "BTN8982") (pin "P$1") (pinfunction "OUT1_P$1") (pintype "bidirectional"))
      (node (ref "BTN8982") (pin "P$5") (pinfunction "OUT2_P$5") (pintype "bidirectional"))
      (node (ref "DIODE") (pin "P$1") (pinfunction "P$1_P$1") (pintype "bidirectional"))
      (node (ref "MTR") (pin "P$10") (pinfunction "+_P$10") (pintype "bidirectional"))
      (node (ref "MTR") (pin "P$11") (pinfunction "+_P$11") (pintype "bidirectional"))
      (node (ref "MTR") (pin "P$12") (pinfunction "+_P$12") (pintype "bidirectional"))
      (node (ref "MTR") (pin "P$13") (pinfunction "+_P$13") (pintype "bidirectional"))
      (node (ref "MTR") (pin "P$14") (pinfunction "+_P$14") (pintype "bidirectional"))
      (node (ref "MTR") (pin "P$2") (pinfunction "+_P$2") (pintype "bidirectional"))
      (node (ref "MTR") (pin "P$7") (pinfunction "+_P$7") (pintype "bidirectional"))
      (node (ref "MTR") (pin "P$8") (pinfunction "+_P$8") (pintype "bidirectional"))
      (node (ref "MTR") (pin "P$9") (pinfunction "+_P$9") (pintype "bidirectional"))
      (node (ref "U$4") (pin "P$1") (pinfunction "P$1_P$1") (pintype "bidirectional"))
      (node (ref "U$4") (pin "P$2") (pinfunction "P$2_P$2") (pintype "bidirectional"))
    )
    (net (code "25") (name "Net-(BTN8982-SR)") (class "Default")
      (node (ref "BTN8982") (pin "P$6") (pinfunction "SR_P$6") (pintype "bidirectional"))
      (node (ref "C4") (pin "1") (pinfunction "1_1") (pintype "passive"))
      (node (ref "R3") (pin "2") (pinfunction "2_2") (pintype "passive"))
    )
    (net (code "26") (name "Net-(C8-Pad1)") (class "Default")
      (node (ref "C8") (pin "1") (pinfunction "1_1") (pintype "passive"))
      (node (ref "TPS82130_5V") (pin "SS/TR") (pinfunction "SS/TR_SS/TR") (pintype "bidirectional"))
    )
    (net (code "27") (name "Net-(C9-Pad1)") (class "Default")
      (node (ref "C9") (pin "1") (pinfunction "1_1") (pintype "passive"))
      (node (ref "TPS82130_3V3") (pin "SS/TR") (pinfunction "SS/TR_SS/TR") (pintype "bidirectional"))
    )
    (net (code "28") (name "Net-(C_VC1-Pad1)") (class "Default")
      (node (ref "C_VC1") (pin "1") (pinfunction "1_1") (pintype "passive"))
      (node (ref "STM32F4X5RG") (pin "VCAP_2") (pinfunction "VCAP_2_VCAP_2") (pintype "bidirectional"))
    )
    (net (code "29") (name "Net-(C_VC2-Pad1)") (class "Default")
      (node (ref "C_VC2") (pin "1") (pinfunction "1_1") (pintype "passive"))
      (node (ref "STM32F4X5RG") (pin "VCAP_1") (pinfunction "VCAP_1_VCAP_1") (pintype "bidirectional"))
    )
    (net (code "30") (name "Net-(LED1-PadA)") (class "Default")
      (node (ref "LED1") (pin "A") (pinfunction "A_A") (pintype "passive"))
      (node (ref "R_L1") (pin "1") (pinfunction "1_1") (pintype "passive"))
    )
    (net (code "31") (name "Net-(LED2-PadA)") (class "Default")
      (node (ref "LED2") (pin "A") (pinfunction "A_A") (pintype "passive"))
      (node (ref "R_L2") (pin "1") (pinfunction "1_1") (pintype "passive"))
    )
    (net (code "32") (name "Net-(LED3-PadA)") (class "Default")
      (node (ref "LED3") (pin "A") (pinfunction "A_A") (pintype "passive"))
      (node (ref "R_L3") (pin "1") (pinfunction "1_1") (pintype "passive"))
    )
    (net (code "33") (name "Net-(LED4-PadA)") (class "Default")
      (node (ref "LED4") (pin "A") (pinfunction "A_A") (pintype "passive"))
      (node (ref "R_L4") (pin "1") (pinfunction "1_1") (pintype "passive"))
    )
    (net (code "34") (name "Net-(PWR_LED-PadA)") (class "Default")
      (node (ref "PWR_LED") (pin "A") (pinfunction "A_A") (pintype "passive"))
      (node (ref "R_PWR") (pin "1") (pinfunction "1_1") (pintype "passive"))
    )
    (net (code "35") (name "Net-(RFB1-Pad1)") (class "Default")
      (node (ref "RFB1") (pin "1") (pinfunction "1_1") (pintype "passive"))
      (node (ref "RFB2") (pin "2") (pinfunction "2_2") (pintype "passive"))
      (node (ref "TPS82130_3V3") (pin "FB") (pinfunction "FB_FB") (pintype "bidirectional"))
    )
    (net (code "36") (name "Net-(RFB3-Pad1)") (class "Default")
      (node (ref "RFB3") (pin "1") (pinfunction "1_1") (pintype "passive"))
      (node (ref "RFB4") (pin "2") (pinfunction "2_2") (pintype "passive"))
      (node (ref "TPS82130_5V") (pin "FB") (pinfunction "FB_FB") (pintype "bidirectional"))
    )
    (net (code "37") (name "OUT_1") (class "Default")
      (node (ref "CAM1") (pin "4") (pinfunction "4_4") (pintype "passive"))
      (node (ref "STM32F4X5RG") (pin "PC5") (pinfunction "PC5_PC5") (pintype "bidirectional"))
    )
    (net (code "38") (name "OUT_2") (class "Default")
      (node (ref "CAM2") (pin "4") (pinfunction "4_4") (pintype "passive"))
      (node (ref "STM32F4X5RG") (pin "PB1") (pinfunction "PB1_PB1") (pintype "bidirectional"))
    )
    (net (code "39") (name "RS") (class "Default")
      (node (ref "HCMS-390X") (pin "RS") (pinfunction "RS_RS") (pintype "bidirectional"))
      (node (ref "STM32F4X5RG") (pin "PB14") (pinfunction "PB14_PB14") (pintype "bidirectional"))
    )
    (net (code "40") (name "RX") (class "Default")
      (node (ref "STM32F4X5RG") (pin "PA10") (pinfunction "PA10_PA10") (pintype "bidirectional"))
      (node (ref "TX-RX-GND-3V3") (pin "2") (pinfunction "2_2") (pintype "passive"))
    )
    (net (code "41") (name "SERVO1") (class "Default")
      (node (ref "SERVO1") (pin "1") (pinfunction "1_1") (pintype "passive"))
      (node (ref "STM32F4X5RG") (pin "PB9") (pinfunction "PB9_PB9") (pintype "bidirectional"))
    )
    (net (code "42") (name "SERVO2") (class "Default")
      (node (ref "SERVO2") (pin "1") (pinfunction "1_1") (pintype "passive"))
      (node (ref "STM32F4X5RG") (pin "PB8") (pinfunction "PB8_PB8") (pintype "bidirectional"))
    )
    (net (code "43") (name "SERVO3") (class "Default")
      (node (ref "SERVO3") (pin "1") (pinfunction "1_1") (pintype "passive"))
      (node (ref "STM32F4X5RG") (pin "PB7") (pinfunction "PB7_PB7") (pintype "bidirectional"))
    )
    (net (code "44") (name "SERVO_EN") (class "Default")
      (node (ref "RFB5") (pin "2") (pinfunction "2_2") (pintype "passive"))
      (node (ref "STM32F4X5RG") (pin "PB3") (pinfunction "PB3_PB3") (pintype "bidirectional"))
      (node (ref "TPS82130_5V") (pin "EN") (pinfunction "EN_EN") (pintype "bidirectional"))
    )
    (net (code "45") (name "SI") (class "Default")
      (node (ref "CAM1") (pin "6") (pinfunction "6_6") (pintype "passive"))
      (node (ref "CAM2") (pin "6") (pinfunction "6_6") (pintype "passive"))
      (node (ref "STM32F4X5RG") (pin "PC8") (pinfunction "PC8_PC8") (pintype "bidirectional"))
    )
    (net (code "46") (name "SWCLK") (class "Default")
      (node (ref "STM32F4X5RG") (pin "PA14") (pinfunction "PA14_PA14") (pintype "bidirectional"))
      (node (ref "SWDIO-GND-SWCLK-3V3") (pin "3") (pinfunction "3_3") (pintype "passive"))
    )
    (net (code "47") (name "SWDIO") (class "Default")
      (node (ref "STM32F4X5RG") (pin "PA13") (pinfunction "PA13_PA13") (pintype "bidirectional"))
      (node (ref "SWDIO-GND-SWCLK-3V3") (pin "1") (pinfunction "1_1") (pintype "passive"))
    )
    (net (code "48") (name "TX") (class "Default")
      (node (ref "STM32F4X5RG") (pin "PA9") (pinfunction "PA9_PA9") (pintype "bidirectional"))
      (node (ref "TX-RX-GND-3V3") (pin "1") (pinfunction "1_1") (pintype "passive"))
    )
    (net (code "49") (name "V+") (class "Default")
      (node (ref "BAT") (pin "P$10") (pinfunction "+_P$10") (pintype "bidirectional"))
      (node (ref "BAT") (pin "P$11") (pinfunction "+_P$11") (pintype "bidirectional"))
      (node (ref "BAT") (pin "P$12") (pinfunction "+_P$12") (pintype "bidirectional"))
      (node (ref "BAT") (pin "P$13") (pinfunction "+_P$13") (pintype "bidirectional"))
      (node (ref "BAT") (pin "P$14") (pinfunction "+_P$14") (pintype "bidirectional"))
      (node (ref "BAT") (pin "P$2") (pinfunction "+_P$2") (pintype "bidirectional"))
      (node (ref "BAT") (pin "P$7") (pinfunction "+_P$7") (pintype "bidirectional"))
      (node (ref "BAT") (pin "P$8") (pinfunction "+_P$8") (pintype "bidirectional"))
      (node (ref "BAT") (pin "P$9") (pinfunction "+_P$9") (pintype "bidirectional"))
      (node (ref "BTN8982") (pin "P$8") (pinfunction "VS_P$8") (pintype "bidirectional"))
      (node (ref "C1") (pin "+") (pinfunction "+_+") (pintype "passive"))
      (node (ref "C12") (pin "1") (pinfunction "1_1") (pintype "passive"))
      (node (ref "C13") (pin "1") (pinfunction "1_1") (pintype "passive"))
      (node (ref "C14") (pin "1") (pinfunction "1_1") (pintype "passive"))
      (node (ref "C19") (pin "1") (pinfunction "1_1") (pintype "passive"))
      (node (ref "C2") (pin "+") (pinfunction "+_+") (pintype "passive"))
      (node (ref "C20") (pin "1") (pinfunction "1_1") (pintype "passive"))
      (node (ref "C25") (pin "+") (pinfunction "+_+") (pintype "passive"))
      (node (ref "C3") (pin "+") (pinfunction "+_+") (pintype "passive"))
      (node (ref "R_VMTR+") (pin "2") (pinfunction "2_2") (pintype "passive"))
      (node (ref "TPS82130_3V3") (pin "EN") (pinfunction "EN_EN") (pintype "bidirectional"))
      (node (ref "TPS82130_3V3") (pin "VIN") (pinfunction "VIN_VIN") (pintype "bidirectional"))
      (node (ref "TPS82130_5V") (pin "VIN") (pinfunction "VIN_VIN") (pintype "bidirectional"))
    )
    (net (code "50") (name "V-") (class "Default")
      (node (ref "BAT") (pin "P$1") (pinfunction "-_P$1") (pintype "bidirectional"))
      (node (ref "BAT") (pin "P$15") (pinfunction "-_P$15") (pintype "bidirectional"))
      (node (ref "BAT") (pin "P$16") (pinfunction "-_P$16") (pintype "bidirectional"))
      (node (ref "BAT") (pin "P$17") (pinfunction "-_P$17") (pintype "bidirectional"))
      (node (ref "BAT") (pin "P$18") (pinfunction "-_P$18") (pintype "bidirectional"))
      (node (ref "BAT") (pin "P$3") (pinfunction "-_P$3") (pintype "bidirectional"))
      (node (ref "BAT") (pin "P$4") (pinfunction "-_P$4") (pintype "bidirectional"))
      (node (ref "BAT") (pin "P$5") (pinfunction "-_P$5") (pintype "bidirectional"))
      (node (ref "BAT") (pin "P$6") (pinfunction "-_P$6") (pintype "bidirectional"))
      (node (ref "BTN8982") (pin "P$2") (pinfunction "GND_P$2") (pintype "bidirectional"))
      (node (ref "C1") (pin "-") (pinfunction "-_-") (pintype "passive"))
      (node (ref "C12") (pin "2") (pinfunction "2_2") (pintype "passive"))
      (node (ref "C2") (pin "-") (pinfunction "-_-") (pintype "passive"))
      (node (ref "C3") (pin "-") (pinfunction "-_-") (pintype "passive"))
      (node (ref "C4") (pin "2") (pinfunction "2_2") (pintype "passive"))
      (node (ref "C5") (pin "2") (pinfunction "2_2") (pintype "passive"))
      (node (ref "DIODE") (pin "P$2") (pinfunction "P$2_P$2") (pintype "bidirectional"))
      (node (ref "MTR") (pin "P$1") (pinfunction "-_P$1") (pintype "bidirectional"))
      (node (ref "MTR") (pin "P$15") (pinfunction "-_P$15") (pintype "bidirectional"))
      (node (ref "MTR") (pin "P$16") (pinfunction "-_P$16") (pintype "bidirectional"))
      (node (ref "MTR") (pin "P$17") (pinfunction "-_P$17") (pintype "bidirectional"))
      (node (ref "MTR") (pin "P$18") (pinfunction "-_P$18") (pintype "bidirectional"))
      (node (ref "MTR") (pin "P$3") (pinfunction "-_P$3") (pintype "bidirectional"))
      (node (ref "MTR") (pin "P$4") (pinfunction "-_P$4") (pintype "bidirectional"))
      (node (ref "MTR") (pin "P$5") (pinfunction "-_P$5") (pintype "bidirectional"))
      (node (ref "MTR") (pin "P$6") (pinfunction "-_P$6") (pintype "bidirectional"))
      (node (ref "ON<-->OFF") (pin "PIN3") (pinfunction "PIN3_PIN3") (pintype "bidirectional"))
      (node (ref "R3") (pin "1") (pinfunction "1_1") (pintype "passive"))
      (node (ref "R4") (pin "1") (pinfunction "1_1") (pintype "passive"))
      (node (ref "R5") (pin "1") (pinfunction "1_1") (pintype "passive"))
    )
    (net (code "51") (name "VMTR") (class "Default")
      (node (ref "R_VMTR+") (pin "1") (pinfunction "1_1") (pintype "passive"))
      (node (ref "R_VMTR-") (pin "2") (pinfunction "2_2") (pintype "passive"))
      (node (ref "STM32F4X5RG") (pin "PC0") (pinfunction "PC0_PC0") (pintype "bidirectional"))
    )
    (net (code "52") (name "unconnected-(ENC-Pad5)") (class "Default")
      (node (ref "ENC") (pin "5") (pinfunction "5_5") (pintype "passive"))
    )
    (net (code "53") (name "unconnected-(ENC-Pad6)") (class "Default")
      (node (ref "ENC") (pin "6") (pinfunction "6_6") (pintype "passive"))
    )
    (net (code "54") (name "unconnected-(HCMS-390X-PadDATA_OUT)") (class "Default")
      (node (ref "HCMS-390X") (pin "DATA_OUT") (pinfunction "DATA_OUT_DATA_OUT") (pintype "bidirectional"))
    )
    (net (code "55") (name "unconnected-(HCMS-390X-PadOSC)") (class "Default")
      (node (ref "HCMS-390X") (pin "OSC") (pinfunction "OSC_OSC") (pintype "bidirectional"))
    )
    (net (code "56") (name "unconnected-(STM32F4X5RG-PadPA8)") (class "Default")
      (node (ref "STM32F4X5RG") (pin "PA8") (pinfunction "PA8_PA8") (pintype "bidirectional"))
    )
    (net (code "57") (name "unconnected-(STM32F4X5RG-PadPA11)") (class "Default")
      (node (ref "STM32F4X5RG") (pin "PA11") (pinfunction "PA11_PA11") (pintype "bidirectional"))
    )
    (net (code "58") (name "unconnected-(STM32F4X5RG-PadPA12)") (class "Default")
      (node (ref "STM32F4X5RG") (pin "PA12") (pinfunction "PA12_PA12") (pintype "bidirectional"))
    )
    (net (code "59") (name "unconnected-(STM32F4X5RG-PadPA15)") (class "Default")
      (node (ref "STM32F4X5RG") (pin "PA15") (pinfunction "PA15_PA15") (pintype "bidirectional"))
    )
    (net (code "60") (name "unconnected-(STM32F4X5RG-PadPB4)") (class "Default")
      (node (ref "STM32F4X5RG") (pin "PB4") (pinfunction "PB4_PB4") (pintype "bidirectional"))
    )
    (net (code "61") (name "unconnected-(STM32F4X5RG-PadPB6)") (class "Default")
      (node (ref "STM32F4X5RG") (pin "PB6") (pinfunction "PB6_PB6") (pintype "bidirectional"))
    )
    (net (code "62") (name "unconnected-(STM32F4X5RG-PadPB10)") (class "Default")
      (node (ref "STM32F4X5RG") (pin "PB10") (pinfunction "PB10_PB10") (pintype "bidirectional"))
    )
    (net (code "63") (name "unconnected-(STM32F4X5RG-PadPB11)") (class "Default")
      (node (ref "STM32F4X5RG") (pin "PB11") (pinfunction "PB11_PB11") (pintype "bidirectional"))
    )
    (net (code "64") (name "unconnected-(STM32F4X5RG-PadPB12)") (class "Default")
      (node (ref "STM32F4X5RG") (pin "PB12") (pinfunction "PB12_PB12") (pintype "bidirectional"))
    )
    (net (code "65") (name "unconnected-(STM32F4X5RG-PadPC1)") (class "Default")
      (node (ref "STM32F4X5RG") (pin "PC1") (pinfunction "PC1_PC1") (pintype "bidirectional"))
    )
    (net (code "66") (name "unconnected-(STM32F4X5RG-PadPC3)") (class "Default")
      (node (ref "STM32F4X5RG") (pin "PC3") (pinfunction "PC3_PC3") (pintype "bidirectional"))
    )
    (net (code "67") (name "unconnected-(STM32F4X5RG-PadPC10)") (class "Default")
      (node (ref "STM32F4X5RG") (pin "PC10") (pinfunction "PC10_PC10") (pintype "bidirectional"))
    )
    (net (code "68") (name "unconnected-(STM32F4X5RG-PadPC11)") (class "Default")
      (node (ref "STM32F4X5RG") (pin "PC11") (pinfunction "PC11_PC11") (pintype "bidirectional"))
    )
    (net (code "69") (name "unconnected-(STM32F4X5RG-PadPC12)") (class "Default")
      (node (ref "STM32F4X5RG") (pin "PC12") (pinfunction "PC12_PC12") (pintype "bidirectional"))
    )
    (net (code "70") (name "unconnected-(STM32F4X5RG-PadPC13)") (class "Default")
      (node (ref "STM32F4X5RG") (pin "PC13") (pinfunction "PC13_PC13") (pintype "bidirectional"))
    )
    (net (code "71") (name "unconnected-(STM32F4X5RG-PadPC14)") (class "Default")
      (node (ref "STM32F4X5RG") (pin "PC14") (pinfunction "PC14_PC14") (pintype "bidirectional"))
    )
    (net (code "72") (name "unconnected-(STM32F4X5RG-PadPC15)") (class "Default")
      (node (ref "STM32F4X5RG") (pin "PC15") (pinfunction "PC15_PC15") (pintype "bidirectional"))
    )
    (net (code "73") (name "unconnected-(STM32F4X5RG-PadPD2)") (class "Default")
      (node (ref "STM32F4X5RG") (pin "PD2") (pinfunction "PD2_PD2") (pintype "bidirectional"))
    )
    (net (code "74") (name "unconnected-(STM32F4X5RG-PadPH0)") (class "Default")
      (node (ref "STM32F4X5RG") (pin "PH0") (pinfunction "PH0_PH0") (pintype "bidirectional"))
    )
    (net (code "75") (name "unconnected-(STM32F4X5RG-PadPH1)") (class "Default")
      (node (ref "STM32F4X5RG") (pin "PH1") (pinfunction "PH1_PH1") (pintype "bidirectional"))
    )
    (net (code "76") (name "unconnected-(TPS82130_3V3-PadPG)") (class "Default")
      (node (ref "TPS82130_3V3") (pin "PG") (pinfunction "PG_PG") (pintype "bidirectional"))
    )
    (net (code "77") (name "unconnected-(TPS82130_5V-PadPG)") (class "Default")
      (node (ref "TPS82130_5V") (pin "PG") (pinfunction "PG_PG") (pintype "bidirectional"))
    )
  )
)
